# USB-HUB-2_0.net
KiCad netlist of a schematic drawn in EasyEDA Pro
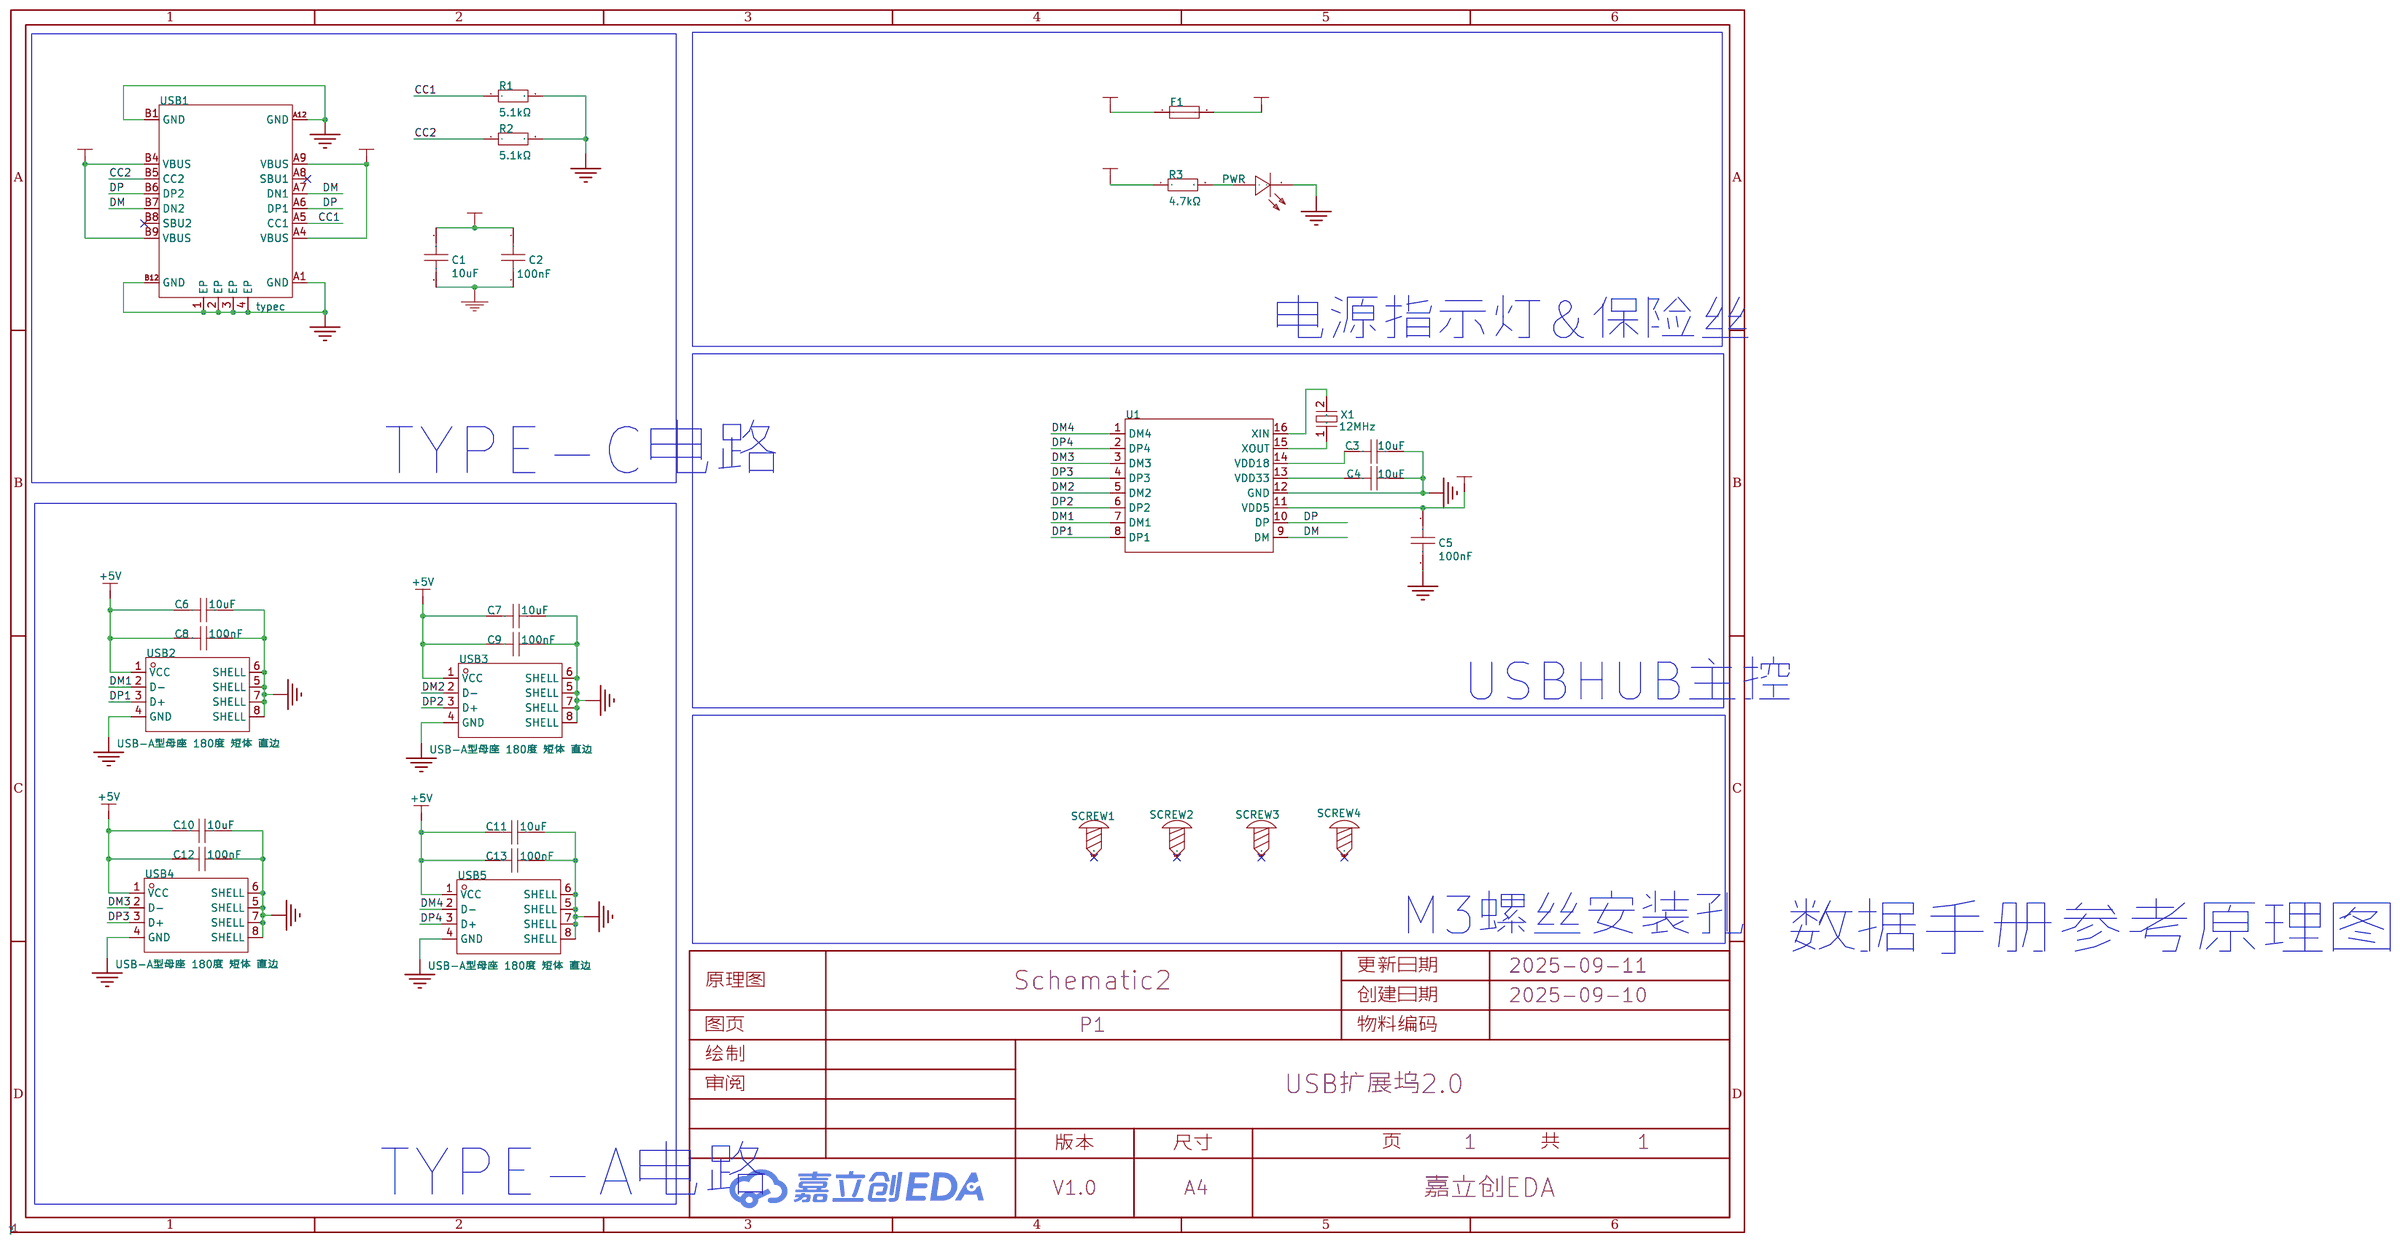
[diagram p0: schematic sheet]

(export (version "E")
  (design (tool "Eeschema 10.0.6"))
  (components
    (comp (ref "C1")
      (value "10uF")
      (fields (field (name "Manufacturer") "SAMSUNG(三星)"))
      (libsource (lib "easyedapro") (part "10uF"))
    )
    (comp (ref "C2")
      (value "100nF")
      (fields (field (name "Manufacturer") "FH(风华)"))
      (libsource (lib "easyedapro") (part "0.1uF"))
    )
    (comp (ref "C3")
      (value "10uF")
      (footprint "easyedapro:C0805")
      (description "容值:10uF;精度:±10%;额定电压:50V;温度系数:X5R;")
      (fields
        (field (name "Manufacturer Part") "CL21A106KBYQNNE")
        (field (name "Manufacturer") "SAMSUNG(三星)")
      )
      (libsource (lib "easyedapro") (part "CL21A106KBYQNNE"))
    )
    (comp (ref "C4")
      (value "10uF")
      (footprint "easyedapro:C0805")
      (description "容值:10uF;精度:±10%;额定电压:50V;温度系数:X5R;")
      (fields
        (field (name "Manufacturer Part") "CL21A106KBYQNNE")
        (field (name "Manufacturer") "SAMSUNG(三星)")
      )
      (libsource (lib "easyedapro") (part "CL21A106KBYQNNE"))
    )
    (comp (ref "C5")
      (value "100nF")
      (fields (field (name "Manufacturer") "FH(风华)"))
      (libsource (lib "easyedapro") (part "0.1uF"))
    )
    (comp (ref "C6")
      (value "10uF")
      (fields (field (name "Manufacturer") "SAMSUNG(三星)"))
      (libsource (lib "easyedapro") (part "10uF"))
    )
    (comp (ref "C7")
      (value "10uF")
      (fields (field (name "Manufacturer") "SAMSUNG(三星)"))
      (libsource (lib "easyedapro") (part "10uF"))
    )
    (comp (ref "C8")
      (value "100nF")
      (fields (field (name "Manufacturer") "FH(风华)"))
      (libsource (lib "easyedapro") (part "0.1uF"))
    )
    (comp (ref "C9")
      (value "100nF")
      (fields (field (name "Manufacturer") "FH(风华)"))
      (libsource (lib "easyedapro") (part "0.1uF"))
    )
    (comp (ref "C10")
      (value "10uF")
      (fields (field (name "Manufacturer") "SAMSUNG(三星)"))
      (libsource (lib "easyedapro") (part "10uF"))
    )
    (comp (ref "C11")
      (value "10uF")
      (fields (field (name "Manufacturer") "SAMSUNG(三星)"))
      (libsource (lib "easyedapro") (part "10uF"))
    )
    (comp (ref "C12")
      (value "100nF")
      (fields (field (name "Manufacturer") "FH(风华)"))
      (libsource (lib "easyedapro") (part "0.1uF"))
    )
    (comp (ref "C13")
      (value "100nF")
      (fields (field (name "Manufacturer") "FH(风华)"))
      (libsource (lib "easyedapro") (part "0.1uF"))
    )
    (comp (ref "F1")
      (value "BSMD1206-150-12V")
      (footprint "easyedapro:F1206")
      (description "耐压(Vmax):12V;最大电流(Imax):40A;保持电流(Ihold):1.5A;跳闸电流(Itrip):3A;")
      (fields (field (name "Manufacturer") "BHFUSE(佰宏)"))
      (libsource (lib "easyedapro") (part "BSMD1206-150-12V"))
    )
    (comp (ref "PWR")
      (value "NCD0805R1")
      (footprint "easyedapro:LED0805-R-RD")
      (fields (field (name "Manufacturer") "国星光电"))
      (libsource (lib "easyedapro") (part "FC-2012HRK-620D"))
    )
    (comp (ref "R1")
      (value "5.1kΩ")
      (footprint "easyedapro:R0805")
      (description "电阻类型:厚膜电阻;阻值:5.1kΩ;精度:±1%;功率:125mW;工作电压:150V;温度系数:±100ppm/°C;")
      (fields
        (field (name "Manufacturer Part") "0805W8F5101T5E")
        (field (name "Manufacturer") "UNI-ROYAL(厚声)")
      )
      (libsource (lib "easyedapro") (part "0805W8F5101T5E"))
    )
    (comp (ref "R2")
      (value "5.1kΩ")
      (footprint "easyedapro:R0805")
      (description "电阻类型:厚膜电阻;阻值:5.1kΩ;精度:±1%;功率:125mW;工作电压:150V;温度系数:±100ppm/°C;")
      (fields
        (field (name "Manufacturer Part") "0805W8F5101T5E")
        (field (name "Manufacturer") "UNI-ROYAL(厚声)")
      )
      (libsource (lib "easyedapro") (part "0805W8F5101T5E"))
    )
    (comp (ref "R3")
      (value "4.7kΩ")
      (footprint "easyedapro:R0805")
      (description "电阻类型:厚膜电阻;阻值:4.7kΩ;精度:±1%;功率:125mW;最大工作电压:150V;温度系数:±100ppm/°C;")
      (fields
        (field (name "Manufacturer Part") "0805W8F4701T5E")
        (field (name "Manufacturer") "UNI-ROYAL(厚声)")
      )
      (libsource (lib "easyedapro") (part "0805W8F4701T5E"))
    )
    (comp (ref "SCREW1")
      (value "~")
      (footprint "easyedapro:M3螺丝")
      (libsource (lib "easyedapro") (part "螺丝孔"))
    )
    (comp (ref "SCREW2")
      (value "~")
      (footprint "easyedapro:M3螺丝")
      (libsource (lib "easyedapro") (part "螺丝孔"))
    )
    (comp (ref "SCREW3")
      (value "~")
      (footprint "easyedapro:M3螺丝")
      (libsource (lib "easyedapro") (part "螺丝孔"))
    )
    (comp (ref "SCREW4")
      (value "~")
      (footprint "easyedapro:M3螺丝")
      (libsource (lib "easyedapro") (part "螺丝孔"))
    )
    (comp (ref "U1") (value "SL2.1A") (libsource (lib "easyedapro") (part "SL2.1A")))
    (comp (ref "USB1")
      (value "typec")
      (footprint "easyedapro:USB-C-SMD_KH-TYPE-C-16P")
      (libsource (lib "easyedapro") (part "TYPEC_C9900016956"))
    )
    (comp (ref "USB2")
      (value "USB-A型母座 180度 短体 直边")
      (footprint "easyedapro:USB-A-SMD_WT_C9900004571")
      (libsource (lib "easyedapro") (part "USB-A型母座 180度 短体 直边"))
    )
    (comp (ref "USB3")
      (value "USB-A型母座 180度 短体 直边")
      (footprint "easyedapro:USB-A-SMD_WT_C9900004571")
      (libsource (lib "easyedapro") (part "USB-A型母座 180度 短体 直边"))
    )
    (comp (ref "USB4")
      (value "USB-A型母座 180度 短体 直边")
      (footprint "easyedapro:USB-A-SMD_WT_C9900004571")
      (libsource (lib "easyedapro") (part "USB-A型母座 180度 短体 直边"))
    )
    (comp (ref "USB5")
      (value "USB-A型母座 180度 短体 直边")
      (footprint "easyedapro:USB-A-SMD_WT_C9900004571")
      (libsource (lib "easyedapro") (part "USB-A型母座 180度 短体 直边"))
    )
    (comp (ref "X1")
      (value "12MHz")
      (footprint "easyedapro:CRYSTAL-SMD_L5.0-W3.2-1")
      (description "频率:12MHz;负载电容:20pF;频率稳定度:±10ppm;")
      (fields
        (field (name "Manufacturer Part") "HY12MSMD5032TCOB1R10")
        (field (name "Manufacturer") "Huiyuan crystal(惠源晶工)")
      )
      (libsource (lib "easyedapro") (part "HY12MSMD5032TCOB1R10"))
    )
  )
  (nets
    (net (code "1") (name "+5V") (class "Default")
      (node (ref "C10") (pin "1") (pinfunction "1_1") (pintype "unspecified"))
      (node (ref "C11") (pin "1") (pinfunction "1_1") (pintype "unspecified"))
      (node (ref "C12") (pin "1") (pinfunction "1_1") (pintype "unspecified"))
      (node (ref "C13") (pin "1") (pinfunction "1_1") (pintype "unspecified"))
      (node (ref "C5") (pin "1") (pinfunction "1_1") (pintype "unspecified"))
      (node (ref "C6") (pin "1") (pinfunction "1_1") (pintype "unspecified"))
      (node (ref "C7") (pin "1") (pinfunction "1_1") (pintype "unspecified"))
      (node (ref "C8") (pin "1") (pinfunction "1_1") (pintype "unspecified"))
      (node (ref "C9") (pin "1") (pinfunction "1_1") (pintype "unspecified"))
      (node (ref "F1") (pin "2") (pinfunction "2_2") (pintype "unspecified"))
      (node (ref "R3") (pin "1") (pinfunction "1_1") (pintype "input"))
      (node (ref "U1") (pin "11") (pinfunction "VDD5_11") (pintype "unspecified"))
      (node (ref "USB2") (pin "1") (pinfunction "VCC_1") (pintype "unspecified"))
      (node (ref "USB3") (pin "1") (pinfunction "VCC_1") (pintype "unspecified"))
      (node (ref "USB4") (pin "1") (pinfunction "VCC_1") (pintype "unspecified"))
      (node (ref "USB5") (pin "1") (pinfunction "VCC_1") (pintype "unspecified"))
    )
    (net (code "2") (name "/CC1") (class "Default")
      (node (ref "R1") (pin "1") (pinfunction "1_1") (pintype "input"))
      (node (ref "USB1") (pin "A5") (pinfunction "CC1_A5") (pintype "unspecified"))
    )
    (net (code "3") (name "/CC2") (class "Default")
      (node (ref "R2") (pin "1") (pinfunction "1_1") (pintype "input"))
      (node (ref "USB1") (pin "B5") (pinfunction "CC2_B5") (pintype "unspecified"))
    )
    (net (code "4") (name "/DM") (class "Default")
      (node (ref "U1") (pin "9") (pinfunction "DM_9") (pintype "unspecified"))
      (node (ref "USB1") (pin "A7") (pinfunction "DN1_A7") (pintype "unspecified"))
      (node (ref "USB1") (pin "B7") (pinfunction "DN2_B7") (pintype "unspecified"))
    )
    (net (code "5") (name "/DM1") (class "Default")
      (node (ref "U1") (pin "7") (pinfunction "DM1_7") (pintype "unspecified"))
      (node (ref "USB2") (pin "2") (pinfunction "D-_2") (pintype "unspecified"))
    )
    (net (code "6") (name "/DM2") (class "Default")
      (node (ref "U1") (pin "5") (pinfunction "DM2_5") (pintype "unspecified"))
      (node (ref "USB3") (pin "2") (pinfunction "D-_2") (pintype "unspecified"))
    )
    (net (code "7") (name "/DM3") (class "Default")
      (node (ref "U1") (pin "3") (pinfunction "DM3_3") (pintype "unspecified"))
      (node (ref "USB4") (pin "2") (pinfunction "D-_2") (pintype "unspecified"))
    )
    (net (code "8") (name "/DM4") (class "Default")
      (node (ref "U1") (pin "1") (pinfunction "DM4_1") (pintype "unspecified"))
      (node (ref "USB5") (pin "2") (pinfunction "D-_2") (pintype "unspecified"))
    )
    (net (code "9") (name "/DP") (class "Default")
      (node (ref "U1") (pin "10") (pinfunction "DP_10") (pintype "unspecified"))
      (node (ref "USB1") (pin "A6") (pinfunction "DP1_A6") (pintype "unspecified"))
      (node (ref "USB1") (pin "B6") (pinfunction "DP2_B6") (pintype "unspecified"))
    )
    (net (code "10") (name "/DP1") (class "Default")
      (node (ref "U1") (pin "8") (pinfunction "DP1_8") (pintype "unspecified"))
      (node (ref "USB2") (pin "3") (pinfunction "D+_3") (pintype "unspecified"))
    )
    (net (code "11") (name "/DP2") (class "Default")
      (node (ref "U1") (pin "6") (pinfunction "DP2_6") (pintype "unspecified"))
      (node (ref "USB3") (pin "3") (pinfunction "D+_3") (pintype "unspecified"))
    )
    (net (code "12") (name "/DP3") (class "Default")
      (node (ref "U1") (pin "4") (pinfunction "DP3_4") (pintype "unspecified"))
      (node (ref "USB4") (pin "3") (pinfunction "D+_3") (pintype "unspecified"))
    )
    (net (code "13") (name "/DP4") (class "Default")
      (node (ref "U1") (pin "2") (pinfunction "DP4_2") (pintype "unspecified"))
      (node (ref "USB5") (pin "3") (pinfunction "D+_3") (pintype "unspecified"))
    )
    (net (code "14") (name "GND") (class "Default")
      (node (ref "C1") (pin "2") (pinfunction "2_2") (pintype "unspecified"))
      (node (ref "C10") (pin "2") (pinfunction "2_2") (pintype "unspecified"))
      (node (ref "C11") (pin "2") (pinfunction "2_2") (pintype "unspecified"))
      (node (ref "C12") (pin "2") (pinfunction "2_2") (pintype "unspecified"))
      (node (ref "C13") (pin "2") (pinfunction "2_2") (pintype "unspecified"))
      (node (ref "C2") (pin "2") (pinfunction "2_2") (pintype "unspecified"))
      (node (ref "C3") (pin "2") (pinfunction "2_2") (pintype "unspecified"))
      (node (ref "C4") (pin "2") (pinfunction "2_2") (pintype "unspecified"))
      (node (ref "C5") (pin "2") (pinfunction "2_2") (pintype "unspecified"))
      (node (ref "C6") (pin "2") (pinfunction "2_2") (pintype "unspecified"))
      (node (ref "C7") (pin "2") (pinfunction "2_2") (pintype "unspecified"))
      (node (ref "C8") (pin "2") (pinfunction "2_2") (pintype "unspecified"))
      (node (ref "C9") (pin "2") (pinfunction "2_2") (pintype "unspecified"))
      (node (ref "PWR") (pin "2") (pinfunction "-_2") (pintype "unspecified"))
      (node (ref "R1") (pin "2") (pinfunction "2_2") (pintype "input"))
      (node (ref "R2") (pin "2") (pinfunction "2_2") (pintype "input"))
      (node (ref "U1") (pin "12") (pinfunction "GND_12") (pintype "unspecified"))
      (node (ref "USB1") (pin "1") (pinfunction "EP_1") (pintype "unspecified"))
      (node (ref "USB1") (pin "2") (pinfunction "EP_2") (pintype "unspecified"))
      (node (ref "USB1") (pin "3") (pinfunction "EP_3") (pintype "unspecified"))
      (node (ref "USB1") (pin "4") (pinfunction "EP_4") (pintype "unspecified"))
      (node (ref "USB1") (pin "A1") (pinfunction "GND_A1") (pintype "unspecified"))
      (node (ref "USB1") (pin "A12") (pinfunction "GND_A12") (pintype "unspecified"))
      (node (ref "USB1") (pin "B1") (pinfunction "GND_B1") (pintype "unspecified"))
      (node (ref "USB1") (pin "B12") (pinfunction "GND_B12") (pintype "unspecified"))
      (node (ref "USB2") (pin "4") (pinfunction "GND_4") (pintype "unspecified"))
      (node (ref "USB2") (pin "5") (pinfunction "SHELL_5") (pintype "unspecified"))
      (node (ref "USB2") (pin "6") (pinfunction "SHELL_6") (pintype "unspecified"))
      (node (ref "USB2") (pin "7") (pinfunction "SHELL_7") (pintype "unspecified"))
      (node (ref "USB2") (pin "8") (pinfunction "SHELL_8") (pintype "unspecified"))
      (node (ref "USB3") (pin "4") (pinfunction "GND_4") (pintype "unspecified"))
      (node (ref "USB3") (pin "5") (pinfunction "SHELL_5") (pintype "unspecified"))
      (node (ref "USB3") (pin "6") (pinfunction "SHELL_6") (pintype "unspecified"))
      (node (ref "USB3") (pin "7") (pinfunction "SHELL_7") (pintype "unspecified"))
      (node (ref "USB3") (pin "8") (pinfunction "SHELL_8") (pintype "unspecified"))
      (node (ref "USB4") (pin "4") (pinfunction "GND_4") (pintype "unspecified"))
      (node (ref "USB4") (pin "5") (pinfunction "SHELL_5") (pintype "unspecified"))
      (node (ref "USB4") (pin "6") (pinfunction "SHELL_6") (pintype "unspecified"))
      (node (ref "USB4") (pin "7") (pinfunction "SHELL_7") (pintype "unspecified"))
      (node (ref "USB4") (pin "8") (pinfunction "SHELL_8") (pintype "unspecified"))
      (node (ref "USB5") (pin "4") (pinfunction "GND_4") (pintype "unspecified"))
      (node (ref "USB5") (pin "5") (pinfunction "SHELL_5") (pintype "unspecified"))
      (node (ref "USB5") (pin "6") (pinfunction "SHELL_6") (pintype "unspecified"))
      (node (ref "USB5") (pin "7") (pinfunction "SHELL_7") (pintype "unspecified"))
      (node (ref "USB5") (pin "8") (pinfunction "SHELL_8") (pintype "unspecified"))
    )
    (net (code "15") (name "Net-(PWR-+)") (class "Default")
      (node (ref "PWR") (pin "1") (pinfunction "+_1") (pintype "unspecified"))
      (node (ref "R3") (pin "2") (pinfunction "2_2") (pintype "input"))
    )
    (net (code "16") (name "Net-(U1-VDD18)") (class "Default")
      (node (ref "C3") (pin "1") (pinfunction "1_1") (pintype "unspecified"))
      (node (ref "U1") (pin "14") (pinfunction "VDD18_14") (pintype "unspecified"))
    )
    (net (code "17") (name "Net-(U1-VDD33)") (class "Default")
      (node (ref "C4") (pin "1") (pinfunction "1_1") (pintype "unspecified"))
      (node (ref "U1") (pin "13") (pinfunction "VDD33_13") (pintype "unspecified"))
    )
    (net (code "18") (name "Net-(U1-XIN)") (class "Default")
      (node (ref "U1") (pin "16") (pinfunction "XIN_16") (pintype "unspecified"))
      (node (ref "X1") (pin "2") (pinfunction "GND_2") (pintype "input"))
    )
    (net (code "19") (name "Net-(U1-XOUT)") (class "Default")
      (node (ref "U1") (pin "15") (pinfunction "XOUT_15") (pintype "unspecified"))
      (node (ref "X1") (pin "1") (pinfunction "1_1") (pintype "input"))
    )
    (net (code "20") (name "VBUS") (class "Default")
      (node (ref "C1") (pin "1") (pinfunction "1_1") (pintype "unspecified"))
      (node (ref "C2") (pin "1") (pinfunction "1_1") (pintype "unspecified"))
      (node (ref "F1") (pin "1") (pinfunction "1_1") (pintype "unspecified"))
      (node (ref "USB1") (pin "A4") (pinfunction "VBUS_A4") (pintype "unspecified"))
      (node (ref "USB1") (pin "A9") (pinfunction "VBUS_A9") (pintype "unspecified"))
      (node (ref "USB1") (pin "B4") (pinfunction "VBUS_B4") (pintype "unspecified"))
      (node (ref "USB1") (pin "B9") (pinfunction "VBUS_B9") (pintype "unspecified"))
    )
    (net (code "21") (name "unconnected-(SCREW1-Pad1)") (class "Default")
      (node (ref "SCREW1") (pin "1") (pinfunction "1_1") (pintype "input+no_connect"))
    )
    (net (code "22") (name "unconnected-(SCREW2-Pad1)") (class "Default")
      (node (ref "SCREW2") (pin "1") (pinfunction "1_1") (pintype "input+no_connect"))
    )
    (net (code "23") (name "unconnected-(SCREW3-Pad1)") (class "Default")
      (node (ref "SCREW3") (pin "1") (pinfunction "1_1") (pintype "input+no_connect"))
    )
    (net (code "24") (name "unconnected-(SCREW4-Pad1)") (class "Default")
      (node (ref "SCREW4") (pin "1") (pinfunction "1_1") (pintype "input+no_connect"))
    )
    (net (code "25") (name "unconnected-(USB1-SBU1-PadA8)") (class "Default")
      (node (ref "USB1") (pin "A8") (pinfunction "SBU1_A8") (pintype "unspecified+no_connect"))
    )
    (net (code "26") (name "unconnected-(USB1-SBU2-PadB8)") (class "Default")
      (node (ref "USB1") (pin "B8") (pinfunction "SBU2_B8") (pintype "unspecified+no_connect"))
    )
  )
)
